# M163A.net
KiCad netlist of a schematic drawn in EAGLE
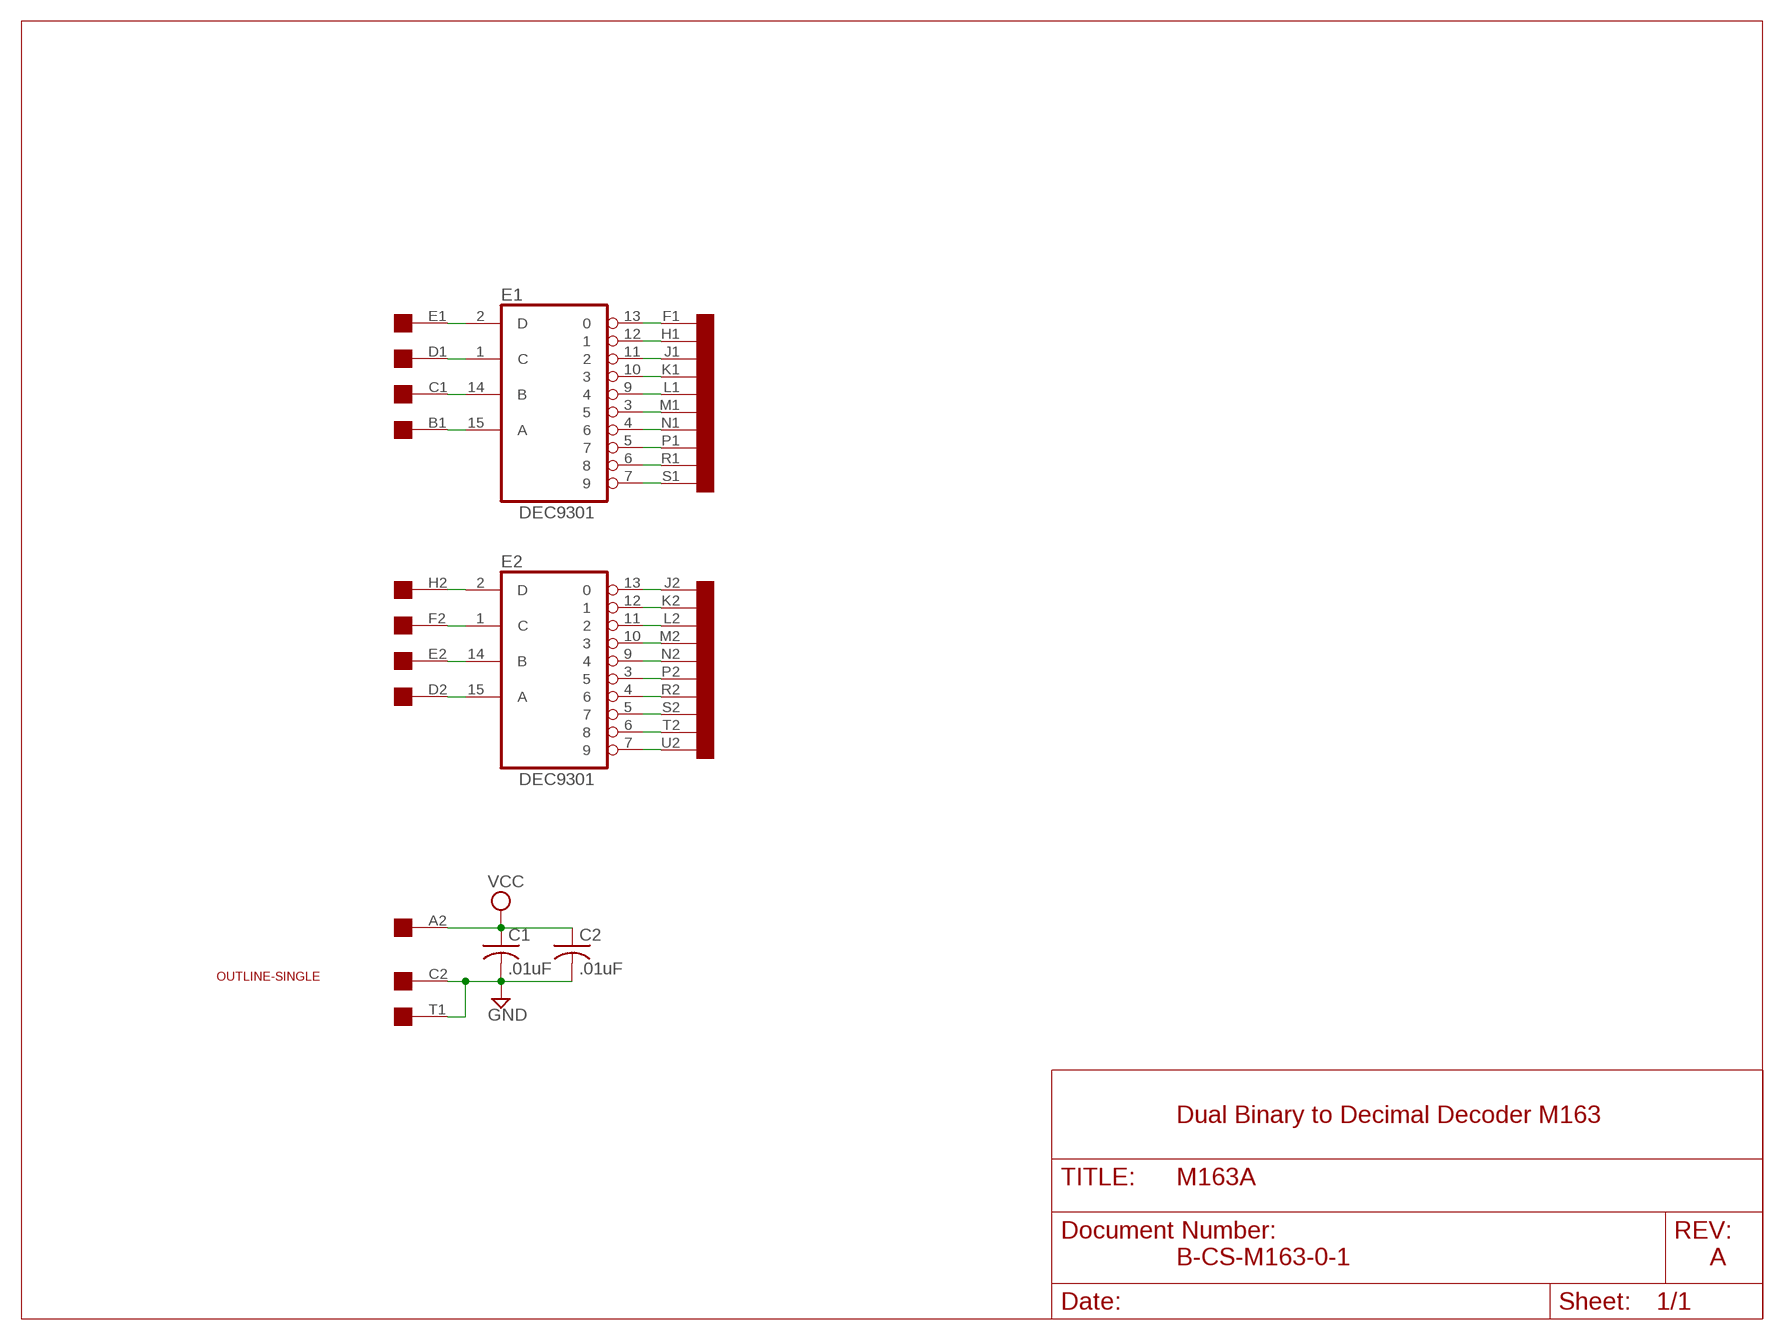
[diagram p0: schematic, sheet 1]

(export (version "E")
  (design (tool "Eeschema 10.0.6"))
  (components
    (comp (ref "C1")
      (value ".01uF")
      (footprint "eagle-import:C050-025X075")
      (libsource (lib "eagle-import") (part "C-US050-025X075"))
    )
    (comp (ref "C2")
      (value ".01uF")
      (footprint "eagle-import:C050-025X075")
      (libsource (lib "eagle-import") (part "C-US050-025X075"))
    )
    (comp (ref "E1")
      (value "DEC9301")
      (footprint "eagle-import:DIL16")
      (libsource (lib "eagle-import") (part "DEC8251"))
    )
    (comp (ref "E2")
      (value "DEC9301")
      (footprint "eagle-import:DIL16")
      (libsource (lib "eagle-import") (part "DEC8251"))
    )
    (comp (ref "U$1")
      (value "OUTLINE-SINGLE")
      (footprint "eagle-import:SINGLE")
      (libsource (lib "eagle-import") (part "OUTLINE-SINGLE"))
    )
    (comp (ref "U$2")
      (value "SINGLE")
      (footprint "eagle-import:EDGE-CON2")
      (libsource (lib "eagle-import") (part "SINGLE"))
    )
  )
  (nets
    (net (code "1") (name "GND") (class "Default")
      (node (ref "C1") (pin "2") (pinfunction "2_2") (pintype "passive"))
      (node (ref "C2") (pin "2") (pinfunction "2_2") (pintype "passive"))
      (node (ref "U$2") (pin "C2") (pinfunction "1_C2") (pintype "bidirectional"))
      (node (ref "U$2") (pin "T1") (pinfunction "1_T1") (pintype "bidirectional"))
    )
    (net (code "2") (name "Net-(E1A-0)") (class "Default")
      (node (ref "E1") (pin "13") (pinfunction "0_13") (pintype "output"))
      (node (ref "U$2") (pin "F1") (pinfunction "1_F1") (pintype "bidirectional"))
    )
    (net (code "3") (name "Net-(E1A-1)") (class "Default")
      (node (ref "E1") (pin "12") (pinfunction "1_12") (pintype "output"))
      (node (ref "U$2") (pin "H1") (pinfunction "1_H1") (pintype "bidirectional"))
    )
    (net (code "4") (name "Net-(E1A-2)") (class "Default")
      (node (ref "E1") (pin "11") (pinfunction "2_11") (pintype "output"))
      (node (ref "U$2") (pin "J1") (pinfunction "1_J1") (pintype "bidirectional"))
    )
    (net (code "5") (name "Net-(E1A-3)") (class "Default")
      (node (ref "E1") (pin "10") (pinfunction "3_10") (pintype "output"))
      (node (ref "U$2") (pin "K1") (pinfunction "1_K1") (pintype "bidirectional"))
    )
    (net (code "6") (name "Net-(E1A-4)") (class "Default")
      (node (ref "E1") (pin "9") (pinfunction "4_9") (pintype "output"))
      (node (ref "U$2") (pin "L1") (pinfunction "1_L1") (pintype "bidirectional"))
    )
    (net (code "7") (name "Net-(E1A-5)") (class "Default")
      (node (ref "E1") (pin "3") (pinfunction "5_3") (pintype "output"))
      (node (ref "U$2") (pin "M1") (pinfunction "1_M1") (pintype "bidirectional"))
    )
    (net (code "8") (name "Net-(E1A-6)") (class "Default")
      (node (ref "E1") (pin "4") (pinfunction "6_4") (pintype "output"))
      (node (ref "U$2") (pin "N1") (pinfunction "1_N1") (pintype "bidirectional"))
    )
    (net (code "9") (name "Net-(E1A-7)") (class "Default")
      (node (ref "E1") (pin "5") (pinfunction "7_5") (pintype "output"))
      (node (ref "U$2") (pin "P1") (pinfunction "1_P1") (pintype "bidirectional"))
    )
    (net (code "10") (name "Net-(E1A-8)") (class "Default")
      (node (ref "E1") (pin "6") (pinfunction "8_6") (pintype "output"))
      (node (ref "U$2") (pin "R1") (pinfunction "1_R1") (pintype "bidirectional"))
    )
    (net (code "11") (name "Net-(E1A-9)") (class "Default")
      (node (ref "E1") (pin "7") (pinfunction "9_7") (pintype "output"))
      (node (ref "U$2") (pin "S1") (pinfunction "1_S1") (pintype "bidirectional"))
    )
    (net (code "12") (name "Net-(E1A-A)") (class "Default")
      (node (ref "E1") (pin "15") (pinfunction "A_15") (pintype "input"))
      (node (ref "U$2") (pin "B1") (pinfunction "1_B1") (pintype "bidirectional"))
    )
    (net (code "13") (name "Net-(E1A-B)") (class "Default")
      (node (ref "E1") (pin "14") (pinfunction "B_14") (pintype "input"))
      (node (ref "U$2") (pin "C1") (pinfunction "1_C1") (pintype "bidirectional"))
    )
    (net (code "14") (name "Net-(E1A-C)") (class "Default")
      (node (ref "E1") (pin "1") (pinfunction "C_1") (pintype "input"))
      (node (ref "U$2") (pin "D1") (pinfunction "1_D1") (pintype "bidirectional"))
    )
    (net (code "15") (name "Net-(E1A-D)") (class "Default")
      (node (ref "E1") (pin "2") (pinfunction "D_2") (pintype "input"))
      (node (ref "U$2") (pin "E1") (pinfunction "1_E1") (pintype "bidirectional"))
    )
    (net (code "16") (name "Net-(E2A-0)") (class "Default")
      (node (ref "E2") (pin "13") (pinfunction "0_13") (pintype "output"))
      (node (ref "U$2") (pin "J2") (pinfunction "1_J2") (pintype "bidirectional"))
    )
    (net (code "17") (name "Net-(E2A-1)") (class "Default")
      (node (ref "E2") (pin "12") (pinfunction "1_12") (pintype "output"))
      (node (ref "U$2") (pin "K2") (pinfunction "1_K2") (pintype "bidirectional"))
    )
    (net (code "18") (name "Net-(E2A-2)") (class "Default")
      (node (ref "E2") (pin "11") (pinfunction "2_11") (pintype "output"))
      (node (ref "U$2") (pin "L2") (pinfunction "1_L2") (pintype "bidirectional"))
    )
    (net (code "19") (name "Net-(E2A-3)") (class "Default")
      (node (ref "E2") (pin "10") (pinfunction "3_10") (pintype "output"))
      (node (ref "U$2") (pin "M2") (pinfunction "1_M2") (pintype "bidirectional"))
    )
    (net (code "20") (name "Net-(E2A-4)") (class "Default")
      (node (ref "E2") (pin "9") (pinfunction "4_9") (pintype "output"))
      (node (ref "U$2") (pin "N2") (pinfunction "1_N2") (pintype "bidirectional"))
    )
    (net (code "21") (name "Net-(E2A-5)") (class "Default")
      (node (ref "E2") (pin "3") (pinfunction "5_3") (pintype "output"))
      (node (ref "U$2") (pin "P2") (pinfunction "1_P2") (pintype "bidirectional"))
    )
    (net (code "22") (name "Net-(E2A-6)") (class "Default")
      (node (ref "E2") (pin "4") (pinfunction "6_4") (pintype "output"))
      (node (ref "U$2") (pin "R2") (pinfunction "1_R2") (pintype "bidirectional"))
    )
    (net (code "23") (name "Net-(E2A-7)") (class "Default")
      (node (ref "E2") (pin "5") (pinfunction "7_5") (pintype "output"))
      (node (ref "U$2") (pin "S2") (pinfunction "1_S2") (pintype "bidirectional"))
    )
    (net (code "24") (name "Net-(E2A-8)") (class "Default")
      (node (ref "E2") (pin "6") (pinfunction "8_6") (pintype "output"))
      (node (ref "U$2") (pin "T2") (pinfunction "1_T2") (pintype "bidirectional"))
    )
    (net (code "25") (name "Net-(E2A-9)") (class "Default")
      (node (ref "E2") (pin "7") (pinfunction "9_7") (pintype "output"))
      (node (ref "U$2") (pin "U2") (pinfunction "1_U2") (pintype "bidirectional"))
    )
    (net (code "26") (name "Net-(E2A-A)") (class "Default")
      (node (ref "E2") (pin "15") (pinfunction "A_15") (pintype "input"))
      (node (ref "U$2") (pin "D2") (pinfunction "1_D2") (pintype "bidirectional"))
    )
    (net (code "27") (name "Net-(E2A-B)") (class "Default")
      (node (ref "E2") (pin "14") (pinfunction "B_14") (pintype "input"))
      (node (ref "U$2") (pin "E2") (pinfunction "1_E2") (pintype "bidirectional"))
    )
    (net (code "28") (name "Net-(E2A-C)") (class "Default")
      (node (ref "E2") (pin "1") (pinfunction "C_1") (pintype "input"))
      (node (ref "U$2") (pin "F2") (pinfunction "1_F2") (pintype "bidirectional"))
    )
    (net (code "29") (name "Net-(E2A-D)") (class "Default")
      (node (ref "E2") (pin "2") (pinfunction "D_2") (pintype "input"))
      (node (ref "U$2") (pin "H2") (pinfunction "1_H2") (pintype "bidirectional"))
    )
    (net (code "30") (name "VCC") (class "Default")
      (node (ref "C1") (pin "1") (pinfunction "1_1") (pintype "passive"))
      (node (ref "C2") (pin "1") (pinfunction "1_1") (pintype "passive"))
      (node (ref "U$2") (pin "A2") (pinfunction "1_A2") (pintype "bidirectional"))
    )
  )
)
